# LEDs.net
KiCad netlist of a schematic drawn in Altium Designer
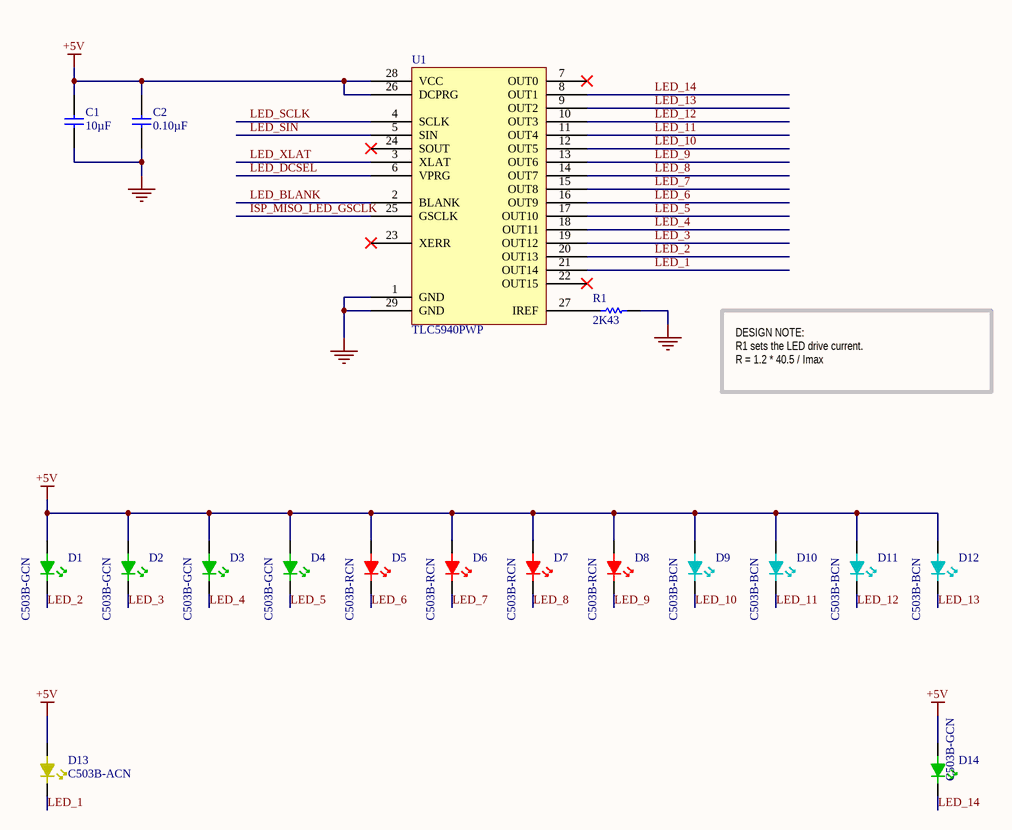
[diagram p0: LEDs.SchDoc]

(export (version "E")
  (design (tool "Eeschema 10.0.6"))
  (components
    (comp (ref "C1")
      (value "10µF")
      (footprint "CAP-0805-M")
      (fields
        (field (name "PART NUMBER") "CC0805KKX7R5BB106")
        (field (name "TOLERANCE") "±10%")
        (field (name "VOLTAGE") "6.3V")
      )
      (libsource (lib "Capacitors") (part "Capacitor"))
    )
    (comp (ref "C2")
      (value "0.10µF")
      (footprint "CAP-0402-M")
      (fields
        (field (name "PART NUMBER") "CC0402KRX7R5BB104")
        (field (name "TOLERANCE") "±10%")
        (field (name "VOLTAGE") "6.3V")
      )
      (libsource (lib "Capacitors") (part "Capacitor"))
    )
    (comp (ref "D1") (value "C503B-GCN") (footprint "LED-5mm-G") (libsource (lib "CANio") (part "C503B-GCN")))
    (comp (ref "D2") (value "C503B-GCN") (footprint "LED-5mm-G") (libsource (lib "CANio") (part "C503B-GCN")))
    (comp (ref "D3") (value "C503B-GCN") (footprint "LED-5mm-G") (libsource (lib "CANio") (part "C503B-GCN")))
    (comp (ref "D4") (value "C503B-GCN") (footprint "LED-5mm-G") (libsource (lib "CANio") (part "C503B-GCN")))
    (comp (ref "D5") (value "C503B-RCN") (footprint "LED-5mm-R") (libsource (lib "CANio") (part "C503B-RCN")))
    (comp (ref "D6") (value "C503B-RCN") (footprint "LED-5mm-R") (libsource (lib "CANio") (part "C503B-RCN")))
    (comp (ref "D7") (value "C503B-RCN") (footprint "LED-5mm-R") (libsource (lib "CANio") (part "C503B-RCN")))
    (comp (ref "D8") (value "C503B-RCN") (footprint "LED-5mm-R") (libsource (lib "CANio") (part "C503B-RCN")))
    (comp (ref "D9") (value "C503B-BCN") (footprint "LED-5mm-B") (libsource (lib "CANio") (part "C503B-BCN")))
    (comp (ref "D10")
      (value "C503B-BCN")
      (footprint "LED-5mm-B")
      (libsource (lib "CANio") (part "C503B-BCN"))
    )
    (comp (ref "D11")
      (value "C503B-BCN")
      (footprint "LED-5mm-B")
      (libsource (lib "CANio") (part "C503B-BCN"))
    )
    (comp (ref "D12")
      (value "C503B-BCN")
      (footprint "LED-5mm-B")
      (libsource (lib "CANio") (part "C503B-BCN"))
    )
    (comp (ref "D13")
      (value "C503B-ACN")
      (footprint "LED-5mm-A")
      (libsource (lib "CANio") (part "C503B-ACN"))
    )
    (comp (ref "D14")
      (value "C503B-GCN")
      (footprint "LED-5mm-G")
      (libsource (lib "CANio") (part "C503B-GCN"))
    )
    (comp (ref "R1")
      (value "2K43")
      (footprint "RES-0603-M")
      (fields
        (field (name "PART NUMBER") "RC0603FR-072K43L")
        (field (name "TOLERANCE") "1%")
        (field (name "POWER") "1/10 W")
      )
      (libsource (lib "Resistors") (part "Resistor"))
    )
    (comp (ref "U1")
      (value "TLC5940PWP")
      (footprint "TSOP65P640X120_HS-29N")
      (libsource (lib "CANwheel") (part "TLC5940PWP"))
    )
  )
  (nets
    (net (code "1") (name "+5V") (class "Default")
      (node (ref "C1") (pin "1") (pinfunction "1_1") (pintype "passive"))
      (node (ref "C2") (pin "1") (pinfunction "1_1") (pintype "passive"))
      (node (ref "D1") (pin "1") (pinfunction "1_1") (pintype "passive"))
      (node (ref "D10") (pin "1") (pinfunction "1_1") (pintype "passive"))
      (node (ref "D11") (pin "1") (pinfunction "1_1") (pintype "passive"))
      (node (ref "D12") (pin "1") (pinfunction "1_1") (pintype "passive"))
      (node (ref "D13") (pin "1") (pinfunction "1_1") (pintype "passive"))
      (node (ref "D14") (pin "1") (pinfunction "1_1") (pintype "passive"))
      (node (ref "D2") (pin "1") (pinfunction "1_1") (pintype "passive"))
      (node (ref "D3") (pin "1") (pinfunction "1_1") (pintype "passive"))
      (node (ref "D4") (pin "1") (pinfunction "1_1") (pintype "passive"))
      (node (ref "D5") (pin "1") (pinfunction "1_1") (pintype "passive"))
      (node (ref "D6") (pin "1") (pinfunction "1_1") (pintype "passive"))
      (node (ref "D7") (pin "1") (pinfunction "1_1") (pintype "passive"))
      (node (ref "D8") (pin "1") (pinfunction "1_1") (pintype "passive"))
      (node (ref "D9") (pin "1") (pinfunction "1_1") (pintype "passive"))
      (node (ref "U1") (pin "26") (pinfunction "DCPRG_26") (pintype "passive"))
      (node (ref "U1") (pin "28") (pinfunction "VCC_28") (pintype "passive"))
    )
    (net (code "2") (name "/ISP_MISO_LED_GSCLK") (class "Default")
      (node (ref "U1") (pin "25") (pinfunction "GSCLK_25") (pintype "passive"))
    )
    (net (code "3") (name "/LED_1") (class "Default")
      (node (ref "D13") (pin "2") (pinfunction "2_2") (pintype "passive"))
      (node (ref "U1") (pin "21") (pinfunction "OUT14_21") (pintype "passive"))
    )
    (net (code "4") (name "/LED_2") (class "Default")
      (node (ref "D1") (pin "2") (pinfunction "2_2") (pintype "passive"))
      (node (ref "U1") (pin "20") (pinfunction "OUT13_20") (pintype "passive"))
    )
    (net (code "5") (name "/LED_3") (class "Default")
      (node (ref "D2") (pin "2") (pinfunction "2_2") (pintype "passive"))
      (node (ref "U1") (pin "19") (pinfunction "OUT12_19") (pintype "passive"))
    )
    (net (code "6") (name "/LED_4") (class "Default")
      (node (ref "D3") (pin "2") (pinfunction "2_2") (pintype "passive"))
      (node (ref "U1") (pin "18") (pinfunction "OUT11_18") (pintype "passive"))
    )
    (net (code "7") (name "/LED_5") (class "Default")
      (node (ref "D4") (pin "2") (pinfunction "2_2") (pintype "passive"))
      (node (ref "U1") (pin "17") (pinfunction "OUT10_17") (pintype "passive"))
    )
    (net (code "8") (name "/LED_6") (class "Default")
      (node (ref "D5") (pin "2") (pinfunction "2_2") (pintype "passive"))
      (node (ref "U1") (pin "16") (pinfunction "OUT9_16") (pintype "passive"))
    )
    (net (code "9") (name "/LED_7") (class "Default")
      (node (ref "D6") (pin "2") (pinfunction "2_2") (pintype "passive"))
      (node (ref "U1") (pin "15") (pinfunction "OUT8_15") (pintype "passive"))
    )
    (net (code "10") (name "/LED_8") (class "Default")
      (node (ref "D7") (pin "2") (pinfunction "2_2") (pintype "passive"))
      (node (ref "U1") (pin "14") (pinfunction "OUT7_14") (pintype "passive"))
    )
    (net (code "11") (name "/LED_9") (class "Default")
      (node (ref "D8") (pin "2") (pinfunction "2_2") (pintype "passive"))
      (node (ref "U1") (pin "13") (pinfunction "OUT6_13") (pintype "passive"))
    )
    (net (code "12") (name "/LED_10") (class "Default")
      (node (ref "D9") (pin "2") (pinfunction "2_2") (pintype "passive"))
      (node (ref "U1") (pin "12") (pinfunction "OUT5_12") (pintype "passive"))
    )
    (net (code "13") (name "/LED_11") (class "Default")
      (node (ref "D10") (pin "2") (pinfunction "2_2") (pintype "passive"))
      (node (ref "U1") (pin "11") (pinfunction "OUT4_11") (pintype "passive"))
    )
    (net (code "14") (name "/LED_12") (class "Default")
      (node (ref "D11") (pin "2") (pinfunction "2_2") (pintype "passive"))
      (node (ref "U1") (pin "10") (pinfunction "OUT3_10") (pintype "passive"))
    )
    (net (code "15") (name "/LED_13") (class "Default")
      (node (ref "D12") (pin "2") (pinfunction "2_2") (pintype "passive"))
      (node (ref "U1") (pin "9") (pinfunction "OUT2_9") (pintype "passive"))
    )
    (net (code "16") (name "/LED_14") (class "Default")
      (node (ref "D14") (pin "2") (pinfunction "2_2") (pintype "passive"))
      (node (ref "U1") (pin "8") (pinfunction "OUT1_8") (pintype "passive"))
    )
    (net (code "17") (name "/LED_BLANK") (class "Default")
      (node (ref "U1") (pin "2") (pinfunction "BLANK_2") (pintype "passive"))
    )
    (net (code "18") (name "/LED_DCSEL") (class "Default")
      (node (ref "U1") (pin "6") (pinfunction "VPRG_6") (pintype "passive"))
    )
    (net (code "19") (name "/LED_SCLK") (class "Default")
      (node (ref "U1") (pin "4") (pinfunction "SCLK_4") (pintype "passive"))
    )
    (net (code "20") (name "/LED_SIN") (class "Default")
      (node (ref "U1") (pin "5") (pinfunction "SIN_5") (pintype "passive"))
    )
    (net (code "21") (name "/LED_XLAT") (class "Default")
      (node (ref "U1") (pin "3") (pinfunction "XLAT_3") (pintype "passive"))
    )
    (net (code "22") (name "GND") (class "Default")
      (node (ref "C1") (pin "2") (pinfunction "2_2") (pintype "passive"))
      (node (ref "C2") (pin "2") (pinfunction "2_2") (pintype "passive"))
      (node (ref "R1") (pin "1") (pinfunction "1_1") (pintype "passive"))
      (node (ref "U1") (pin "1") (pinfunction "GND_1") (pintype "passive"))
      (node (ref "U1") (pin "29") (pinfunction "GND_29") (pintype "passive"))
    )
    (net (code "23") (name "Net-(U1-IREF)") (class "Default")
      (node (ref "R1") (pin "2") (pinfunction "2_2") (pintype "passive"))
      (node (ref "U1") (pin "27") (pinfunction "IREF_27") (pintype "passive"))
    )
    (net (code "24") (name "unconnected-(U1-OUT0-Pad7)") (class "Default")
      (node (ref "U1") (pin "7") (pinfunction "OUT0_7") (pintype "passive+no_connect"))
    )
    (net (code "25") (name "unconnected-(U1-OUT15-Pad22)") (class "Default")
      (node (ref "U1") (pin "22") (pinfunction "OUT15_22") (pintype "passive+no_connect"))
    )
    (net (code "26") (name "unconnected-(U1-SOUT-Pad24)") (class "Default")
      (node (ref "U1") (pin "24") (pinfunction "SOUT_24") (pintype "passive+no_connect"))
    )
    (net (code "27") (name "unconnected-(U1-XERR-Pad23)") (class "Default")
      (node (ref "U1") (pin "23") (pinfunction "XERR_23") (pintype "passive+no_connect"))
    )
  )
)
